# z8530-rs422-b.net
KiCad netlist of a schematic drawn in EAGLE
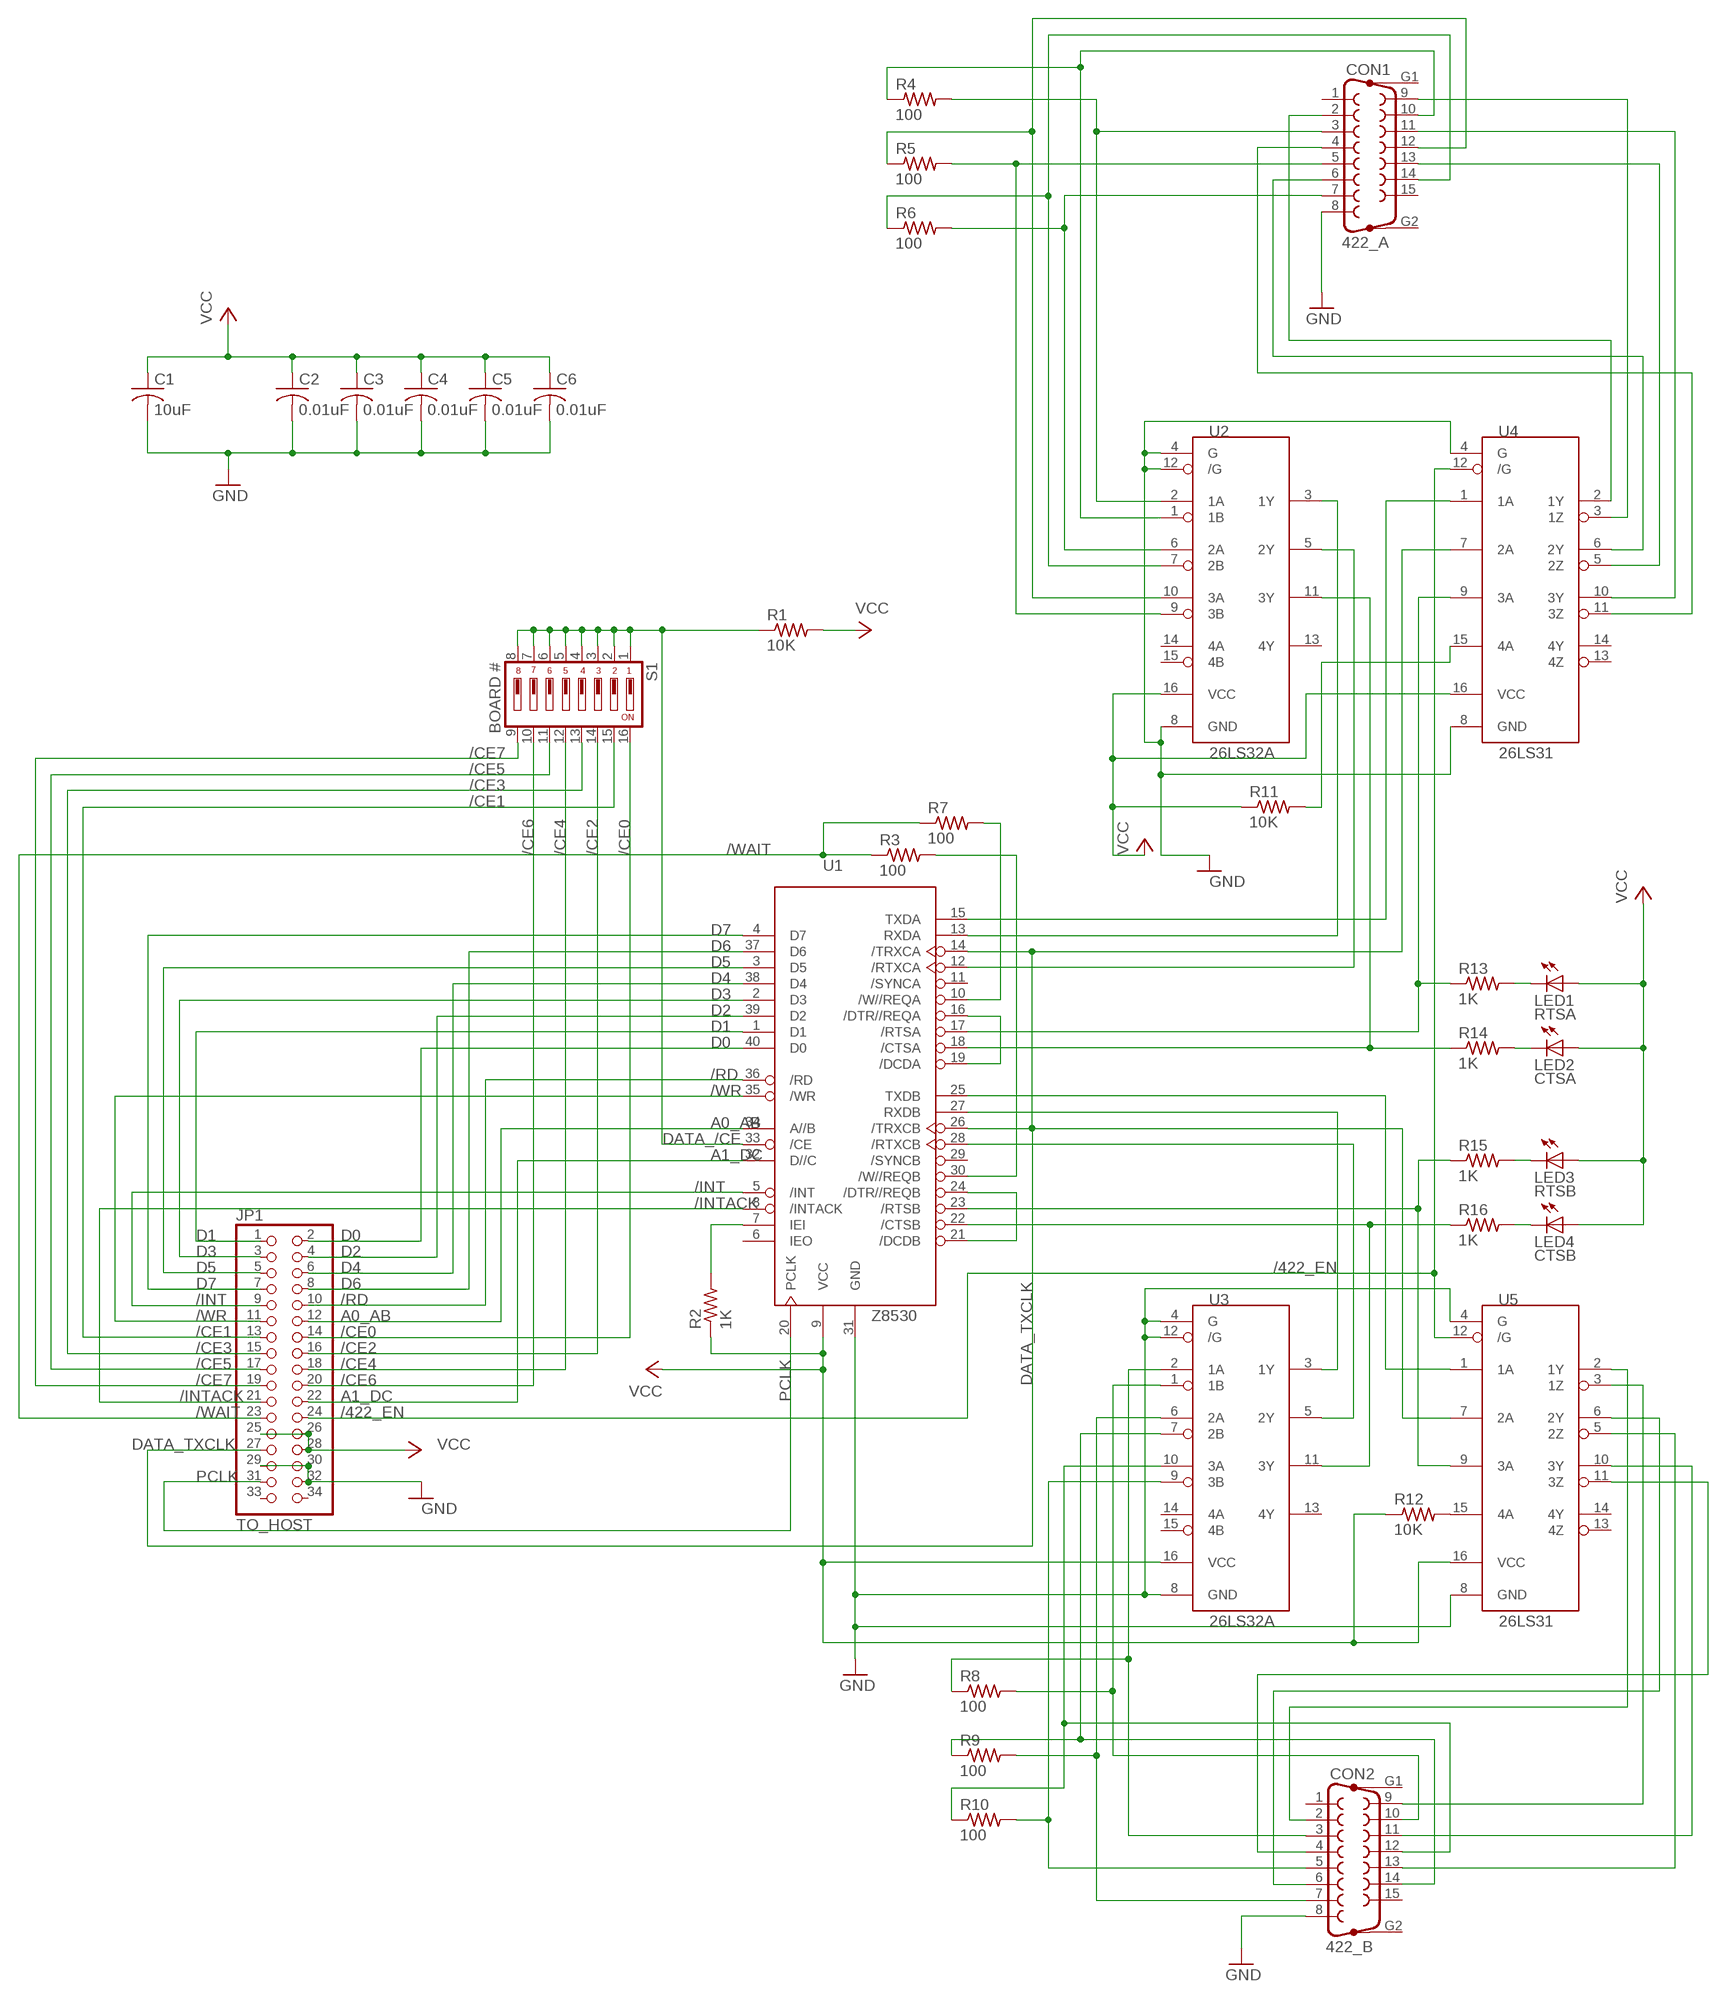
[diagram p0: schematic, sheet 1]

(export (version "E")
  (design (tool "Eeschema 10.0.6"))
  (components
    (comp (ref "C1")
      (value "10uF")
      (footprint "eagle-import:C0805")
      (libsource (lib "eagle-import") (part "C-USC0805"))
    )
    (comp (ref "C2")
      (value "0.01uF")
      (footprint "eagle-import:C0805")
      (libsource (lib "eagle-import") (part "C-USC0805"))
    )
    (comp (ref "C3")
      (value "0.01uF")
      (footprint "eagle-import:C0805")
      (libsource (lib "eagle-import") (part "C-USC0805"))
    )
    (comp (ref "C4")
      (value "0.01uF")
      (footprint "eagle-import:C0805")
      (libsource (lib "eagle-import") (part "C-USC0805"))
    )
    (comp (ref "C5")
      (value "0.01uF")
      (footprint "eagle-import:C0805")
      (libsource (lib "eagle-import") (part "C-USC0805"))
    )
    (comp (ref "C6")
      (value "0.01uF")
      (footprint "eagle-import:C0805")
      (libsource (lib "eagle-import") (part "C-USC0805"))
    )
    (comp (ref "CON1")
      (value "422_A")
      (footprint "eagle-import:F15VP")
      (libsource (lib "eagle-import") (part "F15VP"))
    )
    (comp (ref "CON2")
      (value "422_B")
      (footprint "eagle-import:F15VP")
      (libsource (lib "eagle-import") (part "F15VP"))
    )
    (comp (ref "JP1")
      (value "TO_HOST")
      (footprint "eagle-import:2X17")
      (libsource (lib "eagle-import") (part "PINHD-2X17"))
    )
    (comp (ref "LED1")
      (value "RTSA")
      (footprint "eagle-import:LED3MM")
      (libsource (lib "eagle-import") (part "LED3MM"))
    )
    (comp (ref "LED2")
      (value "CTSA")
      (footprint "eagle-import:LED3MM")
      (libsource (lib "eagle-import") (part "LED3MM"))
    )
    (comp (ref "LED3")
      (value "RTSB")
      (footprint "eagle-import:LED3MM")
      (libsource (lib "eagle-import") (part "LED3MM"))
    )
    (comp (ref "LED4")
      (value "CTSB")
      (footprint "eagle-import:LED3MM")
      (libsource (lib "eagle-import") (part "LED3MM"))
    )
    (comp (ref "R1")
      (value "10K")
      (footprint "eagle-import:R0805")
      (libsource (lib "eagle-import") (part "R-US_R0805"))
    )
    (comp (ref "R2")
      (value "1K")
      (footprint "eagle-import:R0805")
      (libsource (lib "eagle-import") (part "R-US_R0805"))
    )
    (comp (ref "R3")
      (value "100")
      (footprint "eagle-import:R0805")
      (libsource (lib "eagle-import") (part "R-US_R0805"))
    )
    (comp (ref "R4")
      (value "100")
      (footprint "eagle-import:R0805")
      (libsource (lib "eagle-import") (part "R-US_R0805"))
    )
    (comp (ref "R5")
      (value "100")
      (footprint "eagle-import:R0805")
      (libsource (lib "eagle-import") (part "R-US_R0805"))
    )
    (comp (ref "R6")
      (value "100")
      (footprint "eagle-import:R0805")
      (libsource (lib "eagle-import") (part "R-US_R0805"))
    )
    (comp (ref "R7")
      (value "100")
      (footprint "eagle-import:R0805")
      (libsource (lib "eagle-import") (part "R-US_R0805"))
    )
    (comp (ref "R8")
      (value "100")
      (footprint "eagle-import:R0805")
      (libsource (lib "eagle-import") (part "R-US_R0805"))
    )
    (comp (ref "R9")
      (value "100")
      (footprint "eagle-import:R0805")
      (libsource (lib "eagle-import") (part "R-US_R0805"))
    )
    (comp (ref "R10")
      (value "100")
      (footprint "eagle-import:R0805")
      (libsource (lib "eagle-import") (part "R-US_R0805"))
    )
    (comp (ref "R11")
      (value "10K")
      (footprint "eagle-import:R0805")
      (libsource (lib "eagle-import") (part "R-US_R0805"))
    )
    (comp (ref "R12")
      (value "10K")
      (footprint "eagle-import:R0805")
      (libsource (lib "eagle-import") (part "R-US_R0805"))
    )
    (comp (ref "R13")
      (value "1K")
      (footprint "eagle-import:R0805")
      (libsource (lib "eagle-import") (part "R-US_R0805"))
    )
    (comp (ref "R14")
      (value "1K")
      (footprint "eagle-import:R0805")
      (libsource (lib "eagle-import") (part "R-US_R0805"))
    )
    (comp (ref "R15")
      (value "1K")
      (footprint "eagle-import:R0805")
      (libsource (lib "eagle-import") (part "R-US_R0805"))
    )
    (comp (ref "R16")
      (value "1K")
      (footprint "eagle-import:R0805")
      (libsource (lib "eagle-import") (part "R-US_R0805"))
    )
    (comp (ref "S1")
      (value "BOARD #")
      (footprint "eagle-import:DP-08")
      (fields (field (name "MPN") "DP08"))
      (libsource (lib "eagle-import") (part "DP08"))
    )
    (comp (ref "U1")
      (value "Z8530")
      (footprint "eagle-import:DIL40")
      (libsource (lib "eagle-import") (part "Z8530PDIP40"))
    )
    (comp (ref "U2")
      (value "26LS32A")
      (footprint "eagle-import:DIP16")
      (libsource (lib "eagle-import") (part "AM26LS32APDIP16"))
    )
    (comp (ref "U3")
      (value "26LS32A")
      (footprint "eagle-import:DIP16")
      (libsource (lib "eagle-import") (part "AM26LS32APDIP16"))
    )
    (comp (ref "U4")
      (value "26LS31")
      (footprint "eagle-import:DIP16")
      (libsource (lib "eagle-import") (part "AM26L31"))
    )
    (comp (ref "U5")
      (value "26LS31")
      (footprint "eagle-import:DIP16")
      (libsource (lib "eagle-import") (part "AM26L31"))
    )
  )
  (nets
    (net (code "1") (name "/A0_AB") (class "Default")
      (node (ref "JP1") (pin "12") (pinfunction "12_12") (pintype "passive"))
      (node (ref "U1") (pin "34") (pinfunction "A//B_34") (pintype "input"))
    )
    (net (code "2") (name "/A1_DC") (class "Default")
      (node (ref "JP1") (pin "22") (pinfunction "22_22") (pintype "passive"))
      (node (ref "U1") (pin "32") (pinfunction "D//C_32") (pintype "input"))
    )
    (net (code "3") (name "/D0") (class "Default")
      (node (ref "JP1") (pin "2") (pinfunction "2_2") (pintype "passive"))
      (node (ref "U1") (pin "40") (pinfunction "D0_40") (pintype "bidirectional"))
    )
    (net (code "4") (name "/D1") (class "Default")
      (node (ref "JP1") (pin "1") (pinfunction "1_1") (pintype "passive"))
      (node (ref "U1") (pin "1") (pinfunction "D1_1") (pintype "bidirectional"))
    )
    (net (code "5") (name "/D2") (class "Default")
      (node (ref "JP1") (pin "4") (pinfunction "4_4") (pintype "passive"))
      (node (ref "U1") (pin "39") (pinfunction "D2_39") (pintype "bidirectional"))
    )
    (net (code "6") (name "/D3") (class "Default")
      (node (ref "JP1") (pin "3") (pinfunction "3_3") (pintype "passive"))
      (node (ref "U1") (pin "2") (pinfunction "D3_2") (pintype "bidirectional"))
    )
    (net (code "7") (name "/D4") (class "Default")
      (node (ref "JP1") (pin "6") (pinfunction "6_6") (pintype "passive"))
      (node (ref "U1") (pin "38") (pinfunction "D4_38") (pintype "bidirectional"))
    )
    (net (code "8") (name "/D5") (class "Default")
      (node (ref "JP1") (pin "5") (pinfunction "5_5") (pintype "passive"))
      (node (ref "U1") (pin "3") (pinfunction "D5_3") (pintype "bidirectional"))
    )
    (net (code "9") (name "/D6") (class "Default")
      (node (ref "JP1") (pin "8") (pinfunction "8_8") (pintype "passive"))
      (node (ref "U1") (pin "37") (pinfunction "D6_37") (pintype "bidirectional"))
    )
    (net (code "10") (name "/D7") (class "Default")
      (node (ref "JP1") (pin "7") (pinfunction "7_7") (pintype "passive"))
      (node (ref "U1") (pin "4") (pinfunction "D7_4") (pintype "bidirectional"))
    )
    (net (code "11") (name "/DATA_TXCLK") (class "Default")
      (node (ref "JP1") (pin "27") (pinfunction "27_27") (pintype "passive"))
      (node (ref "U1") (pin "14") (pinfunction "/TRXCA_14") (pintype "bidirectional"))
      (node (ref "U1") (pin "26") (pinfunction "/TRXCB_26") (pintype "bidirectional"))
      (node (ref "U4") (pin "7") (pinfunction "2A_7") (pintype "input"))
      (node (ref "U5") (pin "7") (pinfunction "2A_7") (pintype "input"))
    )
    (net (code "12") (name "/DATA_{slash}CE") (class "Default")
      (node (ref "R1") (pin "1") (pinfunction "1_1") (pintype "passive"))
      (node (ref "S1") (pin "1") (pinfunction "1_1") (pintype "passive"))
      (node (ref "S1") (pin "2") (pinfunction "2_2") (pintype "passive"))
      (node (ref "S1") (pin "3") (pinfunction "3_3") (pintype "passive"))
      (node (ref "S1") (pin "4") (pinfunction "4_4") (pintype "passive"))
      (node (ref "S1") (pin "5") (pinfunction "5_5") (pintype "passive"))
      (node (ref "S1") (pin "6") (pinfunction "6_6") (pintype "passive"))
      (node (ref "S1") (pin "7") (pinfunction "7_7") (pintype "passive"))
      (node (ref "S1") (pin "8") (pinfunction "8_8") (pintype "passive"))
      (node (ref "U1") (pin "33") (pinfunction "/CE_33") (pintype "input"))
    )
    (net (code "13") (name "/PCLK") (class "Default")
      (node (ref "JP1") (pin "31") (pinfunction "31_31") (pintype "passive"))
      (node (ref "U1") (pin "20") (pinfunction "PCLK_20") (pintype "input"))
    )
    (net (code "14") (name "/{slash}422_EN") (class "Default")
      (node (ref "JP1") (pin "24") (pinfunction "24_24") (pintype "passive"))
      (node (ref "U4") (pin "12") (pinfunction "/G_12") (pintype "input"))
      (node (ref "U5") (pin "12") (pinfunction "/G_12") (pintype "input"))
    )
    (net (code "15") (name "/{slash}CE0") (class "Default")
      (node (ref "JP1") (pin "14") (pinfunction "14_14") (pintype "passive"))
      (node (ref "S1") (pin "16") (pinfunction "16_16") (pintype "passive"))
    )
    (net (code "16") (name "/{slash}CE1") (class "Default")
      (node (ref "JP1") (pin "13") (pinfunction "13_13") (pintype "passive"))
      (node (ref "S1") (pin "15") (pinfunction "15_15") (pintype "passive"))
    )
    (net (code "17") (name "/{slash}CE2") (class "Default")
      (node (ref "JP1") (pin "16") (pinfunction "16_16") (pintype "passive"))
      (node (ref "S1") (pin "14") (pinfunction "14_14") (pintype "passive"))
    )
    (net (code "18") (name "/{slash}CE3") (class "Default")
      (node (ref "JP1") (pin "15") (pinfunction "15_15") (pintype "passive"))
      (node (ref "S1") (pin "13") (pinfunction "13_13") (pintype "passive"))
    )
    (net (code "19") (name "/{slash}CE4") (class "Default")
      (node (ref "JP1") (pin "18") (pinfunction "18_18") (pintype "passive"))
      (node (ref "S1") (pin "12") (pinfunction "12_12") (pintype "passive"))
    )
    (net (code "20") (name "/{slash}CE5") (class "Default")
      (node (ref "JP1") (pin "17") (pinfunction "17_17") (pintype "passive"))
      (node (ref "S1") (pin "11") (pinfunction "11_11") (pintype "passive"))
    )
    (net (code "21") (name "/{slash}CE6") (class "Default")
      (node (ref "JP1") (pin "20") (pinfunction "20_20") (pintype "passive"))
      (node (ref "S1") (pin "10") (pinfunction "10_10") (pintype "passive"))
    )
    (net (code "22") (name "/{slash}CE7") (class "Default")
      (node (ref "JP1") (pin "19") (pinfunction "19_19") (pintype "passive"))
      (node (ref "S1") (pin "9") (pinfunction "9_9") (pintype "passive"))
    )
    (net (code "23") (name "/{slash}INT") (class "Default")
      (node (ref "JP1") (pin "9") (pinfunction "9_9") (pintype "passive"))
      (node (ref "U1") (pin "5") (pinfunction "/INT_5") (pintype "output"))
    )
    (net (code "24") (name "/{slash}INTACK") (class "Default")
      (node (ref "JP1") (pin "21") (pinfunction "21_21") (pintype "passive"))
      (node (ref "U1") (pin "8") (pinfunction "/INTACK_8") (pintype "input"))
    )
    (net (code "25") (name "/{slash}RD") (class "Default")
      (node (ref "JP1") (pin "10") (pinfunction "10_10") (pintype "passive"))
      (node (ref "U1") (pin "36") (pinfunction "/RD_36") (pintype "input"))
    )
    (net (code "26") (name "/{slash}WAIT") (class "Default")
      (node (ref "JP1") (pin "23") (pinfunction "23_23") (pintype "passive"))
      (node (ref "R3") (pin "1") (pinfunction "1_1") (pintype "passive"))
      (node (ref "R7") (pin "1") (pinfunction "1_1") (pintype "passive"))
    )
    (net (code "27") (name "/{slash}WR") (class "Default")
      (node (ref "JP1") (pin "11") (pinfunction "11_11") (pintype "passive"))
      (node (ref "U1") (pin "35") (pinfunction "/WR_35") (pintype "input"))
    )
    (net (code "28") (name "GND") (class "Default")
      (node (ref "C1") (pin "2") (pinfunction "2_2") (pintype "passive"))
      (node (ref "C2") (pin "2") (pinfunction "2_2") (pintype "passive"))
      (node (ref "C3") (pin "2") (pinfunction "2_2") (pintype "passive"))
      (node (ref "C4") (pin "2") (pinfunction "2_2") (pintype "passive"))
      (node (ref "C5") (pin "2") (pinfunction "2_2") (pintype "passive"))
      (node (ref "C6") (pin "2") (pinfunction "2_2") (pintype "passive"))
      (node (ref "CON1") (pin "8") (pinfunction "8_8") (pintype "passive"))
      (node (ref "CON2") (pin "8") (pinfunction "8_8") (pintype "passive"))
      (node (ref "JP1") (pin "29") (pinfunction "29_29") (pintype "passive"))
      (node (ref "JP1") (pin "30") (pinfunction "30_30") (pintype "passive"))
      (node (ref "JP1") (pin "32") (pinfunction "32_32") (pintype "passive"))
      (node (ref "U1") (pin "31") (pinfunction "GND_31") (pintype "power_in"))
      (node (ref "U2") (pin "12") (pinfunction "/G_12") (pintype "input"))
      (node (ref "U2") (pin "4") (pinfunction "G_4") (pintype "input"))
      (node (ref "U2") (pin "8") (pinfunction "GND_8") (pintype "power_in"))
      (node (ref "U3") (pin "12") (pinfunction "/G_12") (pintype "input"))
      (node (ref "U3") (pin "4") (pinfunction "G_4") (pintype "input"))
      (node (ref "U3") (pin "8") (pinfunction "GND_8") (pintype "power_in"))
      (node (ref "U4") (pin "4") (pinfunction "G_4") (pintype "input"))
      (node (ref "U4") (pin "8") (pinfunction "GND_8") (pintype "power_in"))
      (node (ref "U5") (pin "4") (pinfunction "G_4") (pintype "input"))
      (node (ref "U5") (pin "8") (pinfunction "GND_8") (pintype "power_in"))
    )
    (net (code "29") (name "Net-(LED1-C)") (class "Default")
      (node (ref "LED1") (pin "K") (pinfunction "C_K") (pintype "passive"))
      (node (ref "R13") (pin "2") (pinfunction "2_2") (pintype "passive"))
    )
    (net (code "30") (name "Net-(LED2-C)") (class "Default")
      (node (ref "LED2") (pin "K") (pinfunction "C_K") (pintype "passive"))
      (node (ref "R14") (pin "2") (pinfunction "2_2") (pintype "passive"))
    )
    (net (code "31") (name "Net-(LED3-C)") (class "Default")
      (node (ref "LED3") (pin "K") (pinfunction "C_K") (pintype "passive"))
      (node (ref "R15") (pin "2") (pinfunction "2_2") (pintype "passive"))
    )
    (net (code "32") (name "Net-(LED4-C)") (class "Default")
      (node (ref "LED4") (pin "K") (pinfunction "C_K") (pintype "passive"))
      (node (ref "R16") (pin "2") (pinfunction "2_2") (pintype "passive"))
    )
    (net (code "33") (name "Net-(U1-IEI)") (class "Default")
      (node (ref "R2") (pin "2") (pinfunction "2_2") (pintype "passive"))
      (node (ref "U1") (pin "7") (pinfunction "IEI_7") (pintype "input"))
    )
    (net (code "34") (name "Net-(U1-RXDA)") (class "Default")
      (node (ref "U1") (pin "13") (pinfunction "RXDA_13") (pintype "input"))
      (node (ref "U2") (pin "3") (pinfunction "1Y_3") (pintype "output"))
    )
    (net (code "35") (name "Net-(U1-RXDB)") (class "Default")
      (node (ref "U1") (pin "27") (pinfunction "RXDB_27") (pintype "input"))
      (node (ref "U3") (pin "3") (pinfunction "1Y_3") (pintype "output"))
    )
    (net (code "36") (name "Net-(U1-TXDA)") (class "Default")
      (node (ref "U1") (pin "15") (pinfunction "TXDA_15") (pintype "output"))
      (node (ref "U4") (pin "1") (pinfunction "1A_1") (pintype "input"))
    )
    (net (code "37") (name "Net-(U1-TXDB)") (class "Default")
      (node (ref "U1") (pin "25") (pinfunction "TXDB_25") (pintype "output"))
      (node (ref "U5") (pin "1") (pinfunction "1A_1") (pintype "input"))
    )
    (net (code "38") (name "Net-(U1-{slash}CTSA)") (class "Default")
      (node (ref "R14") (pin "1") (pinfunction "1_1") (pintype "passive"))
      (node (ref "U1") (pin "18") (pinfunction "/CTSA_18") (pintype "input"))
      (node (ref "U2") (pin "11") (pinfunction "3Y_11") (pintype "output"))
    )
    (net (code "39") (name "Net-(U1-{slash}CTSB)") (class "Default")
      (node (ref "R16") (pin "1") (pinfunction "1_1") (pintype "passive"))
      (node (ref "U1") (pin "22") (pinfunction "/CTSB_22") (pintype "input"))
      (node (ref "U3") (pin "11") (pinfunction "3Y_11") (pintype "output"))
    )
    (net (code "40") (name "Net-(U1-{slash}DCDA)") (class "Default")
      (node (ref "U1") (pin "16") (pinfunction "/DTR//REQA_16") (pintype "output"))
      (node (ref "U1") (pin "19") (pinfunction "/DCDA_19") (pintype "input"))
    )
    (net (code "41") (name "Net-(U1-{slash}DCDB)") (class "Default")
      (node (ref "U1") (pin "21") (pinfunction "/DCDB_21") (pintype "input"))
      (node (ref "U1") (pin "24") (pinfunction "/DTR//REQB_24") (pintype "output"))
    )
    (net (code "42") (name "Net-(U1-{slash}RTSA)") (class "Default")
      (node (ref "R13") (pin "1") (pinfunction "1_1") (pintype "passive"))
      (node (ref "U1") (pin "17") (pinfunction "/RTSA_17") (pintype "output"))
      (node (ref "U4") (pin "9") (pinfunction "3A_9") (pintype "input"))
    )
    (net (code "43") (name "Net-(U1-{slash}RTSB)") (class "Default")
      (node (ref "R15") (pin "1") (pinfunction "1_1") (pintype "passive"))
      (node (ref "U1") (pin "23") (pinfunction "/RTSB_23") (pintype "output"))
      (node (ref "U5") (pin "9") (pinfunction "3A_9") (pintype "input"))
    )
    (net (code "44") (name "Net-(U1-{slash}RTXCA)") (class "Default")
      (node (ref "U1") (pin "12") (pinfunction "/RTXCA_12") (pintype "input"))
      (node (ref "U2") (pin "5") (pinfunction "2Y_5") (pintype "output"))
    )
    (net (code "45") (name "Net-(U1-{slash}RTXCB)") (class "Default")
      (node (ref "U1") (pin "28") (pinfunction "/RTXCB_28") (pintype "input"))
      (node (ref "U3") (pin "5") (pinfunction "2Y_5") (pintype "output"))
    )
    (net (code "46") (name "Net-(U1-{slash}W{slash}{slash}REQA)") (class "Default")
      (node (ref "R7") (pin "2") (pinfunction "2_2") (pintype "passive"))
      (node (ref "U1") (pin "10") (pinfunction "/W//REQA_10") (pintype "output"))
    )
    (net (code "47") (name "Net-(U1-{slash}W{slash}{slash}REQB)") (class "Default")
      (node (ref "R3") (pin "2") (pinfunction "2_2") (pintype "passive"))
      (node (ref "U1") (pin "30") (pinfunction "/W//REQB_30") (pintype "output"))
    )
    (net (code "48") (name "Net-(U2-1A)") (class "Default")
      (node (ref "CON1") (pin "3") (pinfunction "3_3") (pintype "passive"))
      (node (ref "R4") (pin "2") (pinfunction "2_2") (pintype "passive"))
      (node (ref "U2") (pin "2") (pinfunction "1A_2") (pintype "input"))
    )
    (net (code "49") (name "Net-(U2-1B)") (class "Default")
      (node (ref "CON1") (pin "10") (pinfunction "10_10") (pintype "passive"))
      (node (ref "R4") (pin "1") (pinfunction "1_1") (pintype "passive"))
      (node (ref "U2") (pin "1") (pinfunction "1B_1") (pintype "input"))
    )
    (net (code "50") (name "Net-(U2-2A)") (class "Default")
      (node (ref "CON1") (pin "7") (pinfunction "7_7") (pintype "passive"))
      (node (ref "R6") (pin "2") (pinfunction "2_2") (pintype "passive"))
      (node (ref "U2") (pin "6") (pinfunction "2A_6") (pintype "input"))
    )
    (net (code "51") (name "Net-(U2-2B)") (class "Default")
      (node (ref "CON1") (pin "14") (pinfunction "14_14") (pintype "passive"))
      (node (ref "R6") (pin "1") (pinfunction "1_1") (pintype "passive"))
      (node (ref "U2") (pin "7") (pinfunction "2B_7") (pintype "input"))
    )
    (net (code "52") (name "Net-(U2-3A)") (class "Default")
      (node (ref "CON1") (pin "12") (pinfunction "12_12") (pintype "passive"))
      (node (ref "R5") (pin "1") (pinfunction "1_1") (pintype "passive"))
      (node (ref "U2") (pin "10") (pinfunction "3A_10") (pintype "input"))
    )
    (net (code "53") (name "Net-(U2-3B)") (class "Default")
      (node (ref "CON1") (pin "5") (pinfunction "5_5") (pintype "passive"))
      (node (ref "R5") (pin "2") (pinfunction "2_2") (pintype "passive"))
      (node (ref "U2") (pin "9") (pinfunction "3B_9") (pintype "input"))
    )
    (net (code "54") (name "Net-(U3-1A)") (class "Default")
      (node (ref "CON2") (pin "3") (pinfunction "3_3") (pintype "passive"))
      (node (ref "R8") (pin "1") (pinfunction "1_1") (pintype "passive"))
      (node (ref "U3") (pin "2") (pinfunction "1A_2") (pintype "input"))
    )
    (net (code "55") (name "Net-(U3-1B)") (class "Default")
      (node (ref "CON2") (pin "10") (pinfunction "10_10") (pintype "passive"))
      (node (ref "R8") (pin "2") (pinfunction "2_2") (pintype "passive"))
      (node (ref "U3") (pin "1") (pinfunction "1B_1") (pintype "input"))
    )
    (net (code "56") (name "Net-(U3-2A)") (class "Default")
      (node (ref "CON2") (pin "7") (pinfunction "7_7") (pintype "passive"))
      (node (ref "R9") (pin "2") (pinfunction "2_2") (pintype "passive"))
      (node (ref "U3") (pin "6") (pinfunction "2A_6") (pintype "input"))
    )
    (net (code "57") (name "Net-(U3-2B)") (class "Default")
      (node (ref "CON2") (pin "14") (pinfunction "14_14") (pintype "passive"))
      (node (ref "R9") (pin "1") (pinfunction "1_1") (pintype "passive"))
      (node (ref "U3") (pin "7") (pinfunction "2B_7") (pintype "input"))
    )
    (net (code "58") (name "Net-(U3-3A)") (class "Default")
      (node (ref "CON2") (pin "12") (pinfunction "12_12") (pintype "passive"))
      (node (ref "R10") (pin "1") (pinfunction "1_1") (pintype "passive"))
      (node (ref "U3") (pin "10") (pinfunction "3A_10") (pintype "input"))
    )
    (net (code "59") (name "Net-(U3-3B)") (class "Default")
      (node (ref "CON2") (pin "5") (pinfunction "5_5") (pintype "passive"))
      (node (ref "R10") (pin "2") (pinfunction "2_2") (pintype "passive"))
      (node (ref "U3") (pin "9") (pinfunction "3B_9") (pintype "input"))
    )
    (net (code "60") (name "Net-(U4-1Y)") (class "Default")
      (node (ref "CON1") (pin "2") (pinfunction "2_2") (pintype "passive"))
      (node (ref "U4") (pin "2") (pinfunction "1Y_2") (pintype "output"))
    )
    (net (code "61") (name "Net-(U4-1Z)") (class "Default")
      (node (ref "CON1") (pin "9") (pinfunction "9_9") (pintype "passive"))
      (node (ref "U4") (pin "3") (pinfunction "1Z_3") (pintype "output"))
    )
    (net (code "62") (name "Net-(U4-2Y)") (class "Default")
      (node (ref "CON1") (pin "6") (pinfunction "6_6") (pintype "passive"))
      (node (ref "U4") (pin "6") (pinfunction "2Y_6") (pintype "output"))
    )
    (net (code "63") (name "Net-(U4-2Z)") (class "Default")
      (node (ref "CON1") (pin "13") (pinfunction "13_13") (pintype "passive"))
      (node (ref "U4") (pin "5") (pinfunction "2Z_5") (pintype "output"))
    )
    (net (code "64") (name "Net-(U4-3Y)") (class "Default")
      (node (ref "CON1") (pin "11") (pinfunction "11_11") (pintype "passive"))
      (node (ref "U4") (pin "10") (pinfunction "3Y_10") (pintype "output"))
    )
    (net (code "65") (name "Net-(U4-3Z)") (class "Default")
      (node (ref "CON1") (pin "4") (pinfunction "4_4") (pintype "passive"))
      (node (ref "U4") (pin "11") (pinfunction "3Z_11") (pintype "output"))
    )
    (net (code "66") (name "Net-(U4-4A)") (class "Default")
      (node (ref "R11") (pin "2") (pinfunction "2_2") (pintype "passive"))
      (node (ref "U4") (pin "15") (pinfunction "4A_15") (pintype "input"))
    )
    (net (code "67") (name "Net-(U5-1Y)") (class "Default")
      (node (ref "CON2") (pin "2") (pinfunction "2_2") (pintype "passive"))
      (node (ref "U5") (pin "2") (pinfunction "1Y_2") (pintype "output"))
    )
    (net (code "68") (name "Net-(U5-1Z)") (class "Default")
      (node (ref "CON2") (pin "9") (pinfunction "9_9") (pintype "passive"))
      (node (ref "U5") (pin "3") (pinfunction "1Z_3") (pintype "output"))
    )
    (net (code "69") (name "Net-(U5-2Y)") (class "Default")
      (node (ref "CON2") (pin "6") (pinfunction "6_6") (pintype "passive"))
      (node (ref "U5") (pin "6") (pinfunction "2Y_6") (pintype "output"))
    )
    (net (code "70") (name "Net-(U5-2Z)") (class "Default")
      (node (ref "CON2") (pin "13") (pinfunction "13_13") (pintype "passive"))
      (node (ref "U5") (pin "5") (pinfunction "2Z_5") (pintype "output"))
    )
    (net (code "71") (name "Net-(U5-3Y)") (class "Default")
      (node (ref "CON2") (pin "11") (pinfunction "11_11") (pintype "passive"))
      (node (ref "U5") (pin "10") (pinfunction "3Y_10") (pintype "output"))
    )
    (net (code "72") (name "Net-(U5-3Z)") (class "Default")
      (node (ref "CON2") (pin "4") (pinfunction "4_4") (pintype "passive"))
      (node (ref "U5") (pin "11") (pinfunction "3Z_11") (pintype "output"))
    )
    (net (code "73") (name "Net-(U5-4A)") (class "Default")
      (node (ref "R12") (pin "2") (pinfunction "2_2") (pintype "passive"))
      (node (ref "U5") (pin "15") (pinfunction "4A_15") (pintype "input"))
    )
    (net (code "74") (name "VCC") (class "Default")
      (node (ref "C1") (pin "1") (pinfunction "1_1") (pintype "passive"))
      (node (ref "C2") (pin "1") (pinfunction "1_1") (pintype "passive"))
      (node (ref "C3") (pin "1") (pinfunction "1_1") (pintype "passive"))
      (node (ref "C4") (pin "1") (pinfunction "1_1") (pintype "passive"))
      (node (ref "C5") (pin "1") (pinfunction "1_1") (pintype "passive"))
      (node (ref "C6") (pin "1") (pinfunction "1_1") (pintype "passive"))
      (node (ref "JP1") (pin "25") (pinfunction "25_25") (pintype "passive"))
      (node (ref "JP1") (pin "26") (pinfunction "26_26") (pintype "passive"))
      (node (ref "JP1") (pin "28") (pinfunction "28_28") (pintype "passive"))
      (node (ref "LED1") (pin "A") (pinfunction "A_A") (pintype "passive"))
      (node (ref "LED2") (pin "A") (pinfunction "A_A") (pintype "passive"))
      (node (ref "LED3") (pin "A") (pinfunction "A_A") (pintype "passive"))
      (node (ref "LED4") (pin "A") (pinfunction "A_A") (pintype "passive"))
      (node (ref "R1") (pin "2") (pinfunction "2_2") (pintype "passive"))
      (node (ref "R11") (pin "1") (pinfunction "1_1") (pintype "passive"))
      (node (ref "R12") (pin "1") (pinfunction "1_1") (pintype "passive"))
      (node (ref "R2") (pin "1") (pinfunction "1_1") (pintype "passive"))
      (node (ref "U1") (pin "9") (pinfunction "VCC_9") (pintype "power_in"))
      (node (ref "U2") (pin "16") (pinfunction "VCC_16") (pintype "power_in"))
      (node (ref "U3") (pin "16") (pinfunction "VCC_16") (pintype "power_in"))
      (node (ref "U4") (pin "16") (pinfunction "VCC_16") (pintype "power_in"))
      (node (ref "U5") (pin "16") (pinfunction "VCC_16") (pintype "power_in"))
    )
    (net (code "75") (name "unconnected-(CON1-Pad1)") (class "Default")
      (node (ref "CON1") (pin "1") (pinfunction "1_1") (pintype "passive"))
    )
    (net (code "76") (name "unconnected-(CON1-Pad15)") (class "Default")
      (node (ref "CON1") (pin "15") (pinfunction "15_15") (pintype "passive"))
    )
    (net (code "77") (name "unconnected-(CON1-PadG1)") (class "Default")
      (node (ref "CON1") (pin "G1") (pinfunction "G1_G1") (pintype "passive"))
    )
    (net (code "78") (name "unconnected-(CON1-PadG2)") (class "Default")
      (node (ref "CON1") (pin "G2") (pinfunction "G2_G2") (pintype "passive"))
    )
    (net (code "79") (name "unconnected-(CON2-Pad1)") (class "Default")
      (node (ref "CON2") (pin "1") (pinfunction "1_1") (pintype "passive"))
    )
    (net (code "80") (name "unconnected-(CON2-Pad15)") (class "Default")
      (node (ref "CON2") (pin "15") (pinfunction "15_15") (pintype "passive"))
    )
    (net (code "81") (name "unconnected-(CON2-PadG1)") (class "Default")
      (node (ref "CON2") (pin "G1") (pinfunction "G1_G1") (pintype "passive"))
    )
    (net (code "82") (name "unconnected-(CON2-PadG2)") (class "Default")
      (node (ref "CON2") (pin "G2") (pinfunction "G2_G2") (pintype "passive"))
    )
    (net (code "83") (name "unconnected-(JP1-Pad33)") (class "Default")
      (node (ref "JP1") (pin "33") (pinfunction "33_33") (pintype "passive"))
    )
    (net (code "84") (name "unconnected-(JP1-Pad34)") (class "Default")
      (node (ref "JP1") (pin "34") (pinfunction "34_34") (pintype "passive"))
    )
    (net (code "85") (name "unconnected-(U1-IEO-Pad6)") (class "Default")
      (node (ref "U1") (pin "6") (pinfunction "IEO_6") (pintype "output"))
    )
    (net (code "86") (name "unconnected-(U1-{slash}SYNCA-Pad11)") (class "Default")
      (node (ref "U1") (pin "11") (pinfunction "/SYNCA_11") (pintype "bidirectional"))
    )
    (net (code "87") (name "unconnected-(U1-{slash}SYNCB-Pad29)") (class "Default")
      (node (ref "U1") (pin "29") (pinfunction "/SYNCB_29") (pintype "bidirectional"))
    )
    (net (code "88") (name "unconnected-(U2-4A-Pad14)") (class "Default")
      (node (ref "U2") (pin "14") (pinfunction "4A_14") (pintype "input"))
    )
    (net (code "89") (name "unconnected-(U2-4B-Pad15)") (class "Default")
      (node (ref "U2") (pin "15") (pinfunction "4B_15") (pintype "input"))
    )
    (net (code "90") (name "unconnected-(U2-4Y-Pad13)") (class "Default")
      (node (ref "U2") (pin "13") (pinfunction "4Y_13") (pintype "output"))
    )
    (net (code "91") (name "unconnected-(U3-4A-Pad14)") (class "Default")
      (node (ref "U3") (pin "14") (pinfunction "4A_14") (pintype "input"))
    )
    (net (code "92") (name "unconnected-(U3-4B-Pad15)") (class "Default")
      (node (ref "U3") (pin "15") (pinfunction "4B_15") (pintype "input"))
    )
    (net (code "93") (name "unconnected-(U3-4Y-Pad13)") (class "Default")
      (node (ref "U3") (pin "13") (pinfunction "4Y_13") (pintype "output"))
    )
    (net (code "94") (name "unconnected-(U4-4Y-Pad14)") (class "Default")
      (node (ref "U4") (pin "14") (pinfunction "4Y_14") (pintype "output"))
    )
    (net (code "95") (name "unconnected-(U4-4Z-Pad13)") (class "Default")
      (node (ref "U4") (pin "13") (pinfunction "4Z_13") (pintype "output"))
    )
    (net (code "96") (name "unconnected-(U5-4Y-Pad14)") (class "Default")
      (node (ref "U5") (pin "14") (pinfunction "4Y_14") (pintype "output"))
    )
    (net (code "97") (name "unconnected-(U5-4Z-Pad13)") (class "Default")
      (node (ref "U5") (pin "13") (pinfunction "4Z_13") (pintype "output"))
    )
  )
)
